# Motorcontroller.net
KiCad netlist of a schematic drawn in EAGLE
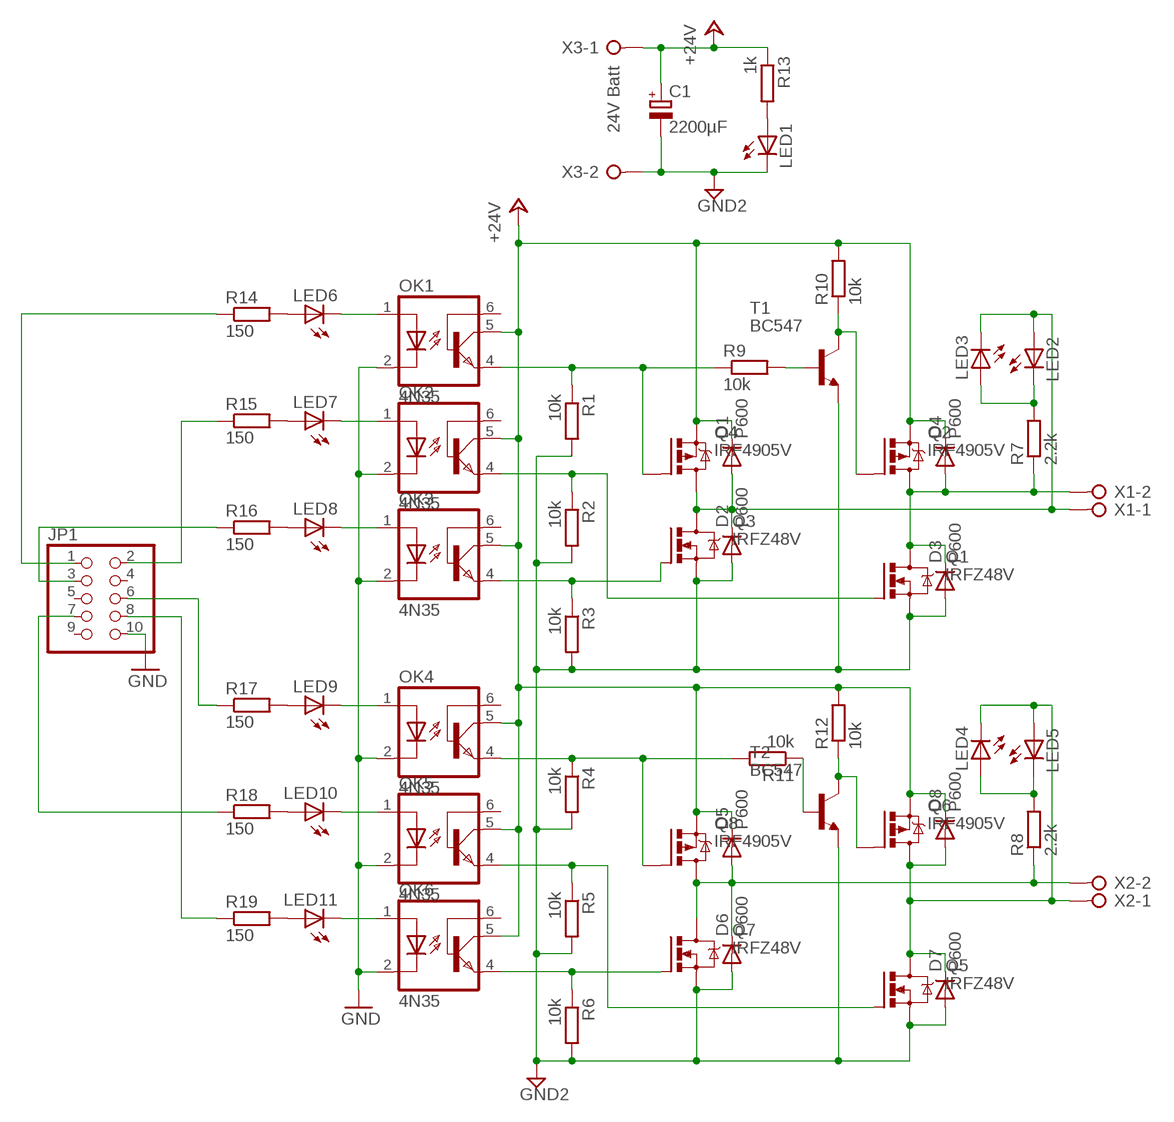
[diagram p0: schematic, sheet 1]

(export (version "E")
  (design (tool "Eeschema 10.0.6"))
  (components
    (comp (ref "C1")
      (value "2200µF")
      (footprint "eagle-import:E5-13")
      (libsource (lib "eagle-import") (part "CPOL-EUE5-13"))
    )
    (comp (ref "D1")
      (value "P600")
      (footprint "eagle-import:P6-15")
      (libsource (lib "eagle-import") (part "P600"))
    )
    (comp (ref "D2")
      (value "P600")
      (footprint "eagle-import:P6-15")
      (libsource (lib "eagle-import") (part "P600"))
    )
    (comp (ref "D3")
      (value "P600")
      (footprint "eagle-import:P6-15")
      (libsource (lib "eagle-import") (part "P600"))
    )
    (comp (ref "D4")
      (value "P600")
      (footprint "eagle-import:P6-15")
      (libsource (lib "eagle-import") (part "P600"))
    )
    (comp (ref "D5")
      (value "P600")
      (footprint "eagle-import:P6-15")
      (libsource (lib "eagle-import") (part "P600"))
    )
    (comp (ref "D6")
      (value "P600")
      (footprint "eagle-import:P6-15")
      (libsource (lib "eagle-import") (part "P600"))
    )
    (comp (ref "D7")
      (value "P600")
      (footprint "eagle-import:P6-15")
      (libsource (lib "eagle-import") (part "P600"))
    )
    (comp (ref "D8")
      (value "P600")
      (footprint "eagle-import:P6-15")
      (libsource (lib "eagle-import") (part "P600"))
    )
    (comp (ref "JP1")
      (value "PINHD-2X5")
      (footprint "eagle-import:2X05")
      (libsource (lib "eagle-import") (part "PINHD-2X5"))
    )
    (comp (ref "LED1")
      (value "LED3MM")
      (footprint "eagle-import:LED3MM")
      (libsource (lib "eagle-import") (part "LED3MM"))
    )
    (comp (ref "LED2")
      (value "LED3MM")
      (footprint "eagle-import:LED3MM")
      (libsource (lib "eagle-import") (part "LED3MM"))
    )
    (comp (ref "LED3")
      (value "LED3MM")
      (footprint "eagle-import:LED3MM")
      (libsource (lib "eagle-import") (part "LED3MM"))
    )
    (comp (ref "LED4")
      (value "LED3MM")
      (footprint "eagle-import:LED3MM")
      (libsource (lib "eagle-import") (part "LED3MM"))
    )
    (comp (ref "LED5")
      (value "LED3MM")
      (footprint "eagle-import:LED3MM")
      (libsource (lib "eagle-import") (part "LED3MM"))
    )
    (comp (ref "LED6")
      (value "LED3MM")
      (footprint "eagle-import:LED3MM")
      (libsource (lib "eagle-import") (part "LED3MM"))
    )
    (comp (ref "LED7")
      (value "LED3MM")
      (footprint "eagle-import:LED3MM")
      (libsource (lib "eagle-import") (part "LED3MM"))
    )
    (comp (ref "LED8")
      (value "LED3MM")
      (footprint "eagle-import:LED3MM")
      (libsource (lib "eagle-import") (part "LED3MM"))
    )
    (comp (ref "LED9")
      (value "LED3MM")
      (footprint "eagle-import:LED3MM")
      (libsource (lib "eagle-import") (part "LED3MM"))
    )
    (comp (ref "LED10")
      (value "LED3MM")
      (footprint "eagle-import:LED3MM")
      (libsource (lib "eagle-import") (part "LED3MM"))
    )
    (comp (ref "LED11")
      (value "LED3MM")
      (footprint "eagle-import:LED3MM")
      (libsource (lib "eagle-import") (part "LED3MM"))
    )
    (comp (ref "OK1")
      (value "4N35")
      (footprint "eagle-import:DIL06")
      (fields (field (name "MF") "FAIRCHILD SEMICONDUCTOR"))
      (libsource (lib "eagle-import") (part "4N35"))
    )
    (comp (ref "OK2")
      (value "4N35")
      (footprint "eagle-import:DIL06")
      (fields (field (name "MF") "FAIRCHILD SEMICONDUCTOR"))
      (libsource (lib "eagle-import") (part "4N35"))
    )
    (comp (ref "OK3")
      (value "4N35")
      (footprint "eagle-import:DIL06")
      (fields (field (name "MF") "FAIRCHILD SEMICONDUCTOR"))
      (libsource (lib "eagle-import") (part "4N35"))
    )
    (comp (ref "OK4")
      (value "4N35")
      (footprint "eagle-import:DIL06")
      (fields (field (name "MF") "FAIRCHILD SEMICONDUCTOR"))
      (libsource (lib "eagle-import") (part "4N35"))
    )
    (comp (ref "OK5")
      (value "4N35")
      (footprint "eagle-import:DIL06")
      (fields (field (name "MF") "FAIRCHILD SEMICONDUCTOR"))
      (libsource (lib "eagle-import") (part "4N35"))
    )
    (comp (ref "OK6")
      (value "4N35")
      (footprint "eagle-import:DIL06")
      (fields (field (name "MF") "FAIRCHILD SEMICONDUCTOR"))
      (libsource (lib "eagle-import") (part "4N35"))
    )
    (comp (ref "Q1")
      (value "IRFZ48V")
      (footprint "eagle-import:TO220BV")
      (libsource (lib "eagle-import") (part "IRFZ48V"))
    )
    (comp (ref "Q2")
      (value "IRF4905V")
      (footprint "eagle-import:TO220BV")
      (libsource (lib "eagle-import") (part "IRF4905V"))
    )
    (comp (ref "Q3")
      (value "IRFZ48V")
      (footprint "eagle-import:TO220BV")
      (libsource (lib "eagle-import") (part "IRFZ48V"))
    )
    (comp (ref "Q4")
      (value "IRF4905V")
      (footprint "eagle-import:TO220BV")
      (libsource (lib "eagle-import") (part "IRF4905V"))
    )
    (comp (ref "Q5")
      (value "IRFZ48V")
      (footprint "eagle-import:TO220BV")
      (libsource (lib "eagle-import") (part "IRFZ48V"))
    )
    (comp (ref "Q6")
      (value "IRF4905V")
      (footprint "eagle-import:TO220BV")
      (libsource (lib "eagle-import") (part "IRF4905V"))
    )
    (comp (ref "Q7")
      (value "IRFZ48V")
      (footprint "eagle-import:TO220BV")
      (libsource (lib "eagle-import") (part "IRFZ48V"))
    )
    (comp (ref "Q8")
      (value "IRF4905V")
      (footprint "eagle-import:TO220BV")
      (libsource (lib "eagle-import") (part "IRF4905V"))
    )
    (comp (ref "R1")
      (value "10k")
      (footprint "eagle-import:0207_7")
      (libsource (lib "eagle-import") (part "R-EU_0207/7"))
    )
    (comp (ref "R2")
      (value "10k")
      (footprint "eagle-import:0207_7")
      (libsource (lib "eagle-import") (part "R-EU_0207/7"))
    )
    (comp (ref "R3")
      (value "10k")
      (footprint "eagle-import:0207_10")
      (libsource (lib "eagle-import") (part "R-EU_0207/10"))
    )
    (comp (ref "R4")
      (value "10k")
      (footprint "eagle-import:0207_10")
      (libsource (lib "eagle-import") (part "R-EU_0207/10"))
    )
    (comp (ref "R5")
      (value "10k")
      (footprint "eagle-import:0207_10")
      (libsource (lib "eagle-import") (part "R-EU_0207/10"))
    )
    (comp (ref "R6")
      (value "10k")
      (footprint "eagle-import:0207_10")
      (libsource (lib "eagle-import") (part "R-EU_0207/10"))
    )
    (comp (ref "R7")
      (value "2.2k")
      (footprint "eagle-import:0207_2V")
      (libsource (lib "eagle-import") (part "R-EU_0207/2V"))
    )
    (comp (ref "R8")
      (value "2.2k")
      (footprint "eagle-import:0207_2V")
      (libsource (lib "eagle-import") (part "R-EU_0207/2V"))
    )
    (comp (ref "R9")
      (value "10k")
      (footprint "eagle-import:0207_7")
      (libsource (lib "eagle-import") (part "R-EU_0207/7"))
    )
    (comp (ref "R10")
      (value "10k")
      (footprint "eagle-import:0207_7")
      (libsource (lib "eagle-import") (part "R-EU_0207/7"))
    )
    (comp (ref "R11")
      (value "10k")
      (footprint "eagle-import:0207_10")
      (libsource (lib "eagle-import") (part "R-EU_0207/10"))
    )
    (comp (ref "R12")
      (value "10k")
      (footprint "eagle-import:0207_10")
      (libsource (lib "eagle-import") (part "R-EU_0207/10"))
    )
    (comp (ref "R13")
      (value "1k")
      (footprint "eagle-import:0207_2V")
      (libsource (lib "eagle-import") (part "R-EU_0207/2V"))
    )
    (comp (ref "R14")
      (value "150")
      (footprint "eagle-import:0207_7")
      (libsource (lib "eagle-import") (part "R-EU_0207/7"))
    )
    (comp (ref "R15")
      (value "150")
      (footprint "eagle-import:0207_5V")
      (libsource (lib "eagle-import") (part "R-EU_0207/5V"))
    )
    (comp (ref "R16")
      (value "150")
      (footprint "eagle-import:0207_5V")
      (libsource (lib "eagle-import") (part "R-EU_0207/5V"))
    )
    (comp (ref "R17")
      (value "150")
      (footprint "eagle-import:0207_5V")
      (libsource (lib "eagle-import") (part "R-EU_0207/5V"))
    )
    (comp (ref "R18")
      (value "150")
      (footprint "eagle-import:0207_5V")
      (libsource (lib "eagle-import") (part "R-EU_0207/5V"))
    )
    (comp (ref "R19")
      (value "150")
      (footprint "eagle-import:0207_7")
      (libsource (lib "eagle-import") (part "R-EU_0207/7"))
    )
    (comp (ref "T1")
      (value "BC547")
      (footprint "eagle-import:TO92")
      (libsource (lib "eagle-import") (part "BC547"))
    )
    (comp (ref "T2")
      (value "BC547")
      (footprint "eagle-import:TO92")
      (libsource (lib "eagle-import") (part "BC547"))
    )
    (comp (ref "X1")
      (value "W237-02P")
      (footprint "eagle-import:W237-132")
      (fields (field (name "OC_FARNELL") "unknown") (field (name "OC_NEWARK") "unknown"))
      (libsource (lib "eagle-import") (part "W237-02P"))
    )
    (comp (ref "X2")
      (value "W237-02P")
      (footprint "eagle-import:W237-132")
      (fields (field (name "OC_FARNELL") "unknown") (field (name "OC_NEWARK") "unknown"))
      (libsource (lib "eagle-import") (part "W237-02P"))
    )
    (comp (ref "X3")
      (value "24V Batt")
      (footprint "eagle-import:W237-132")
      (fields (field (name "OC_FARNELL") "unknown") (field (name "OC_NEWARK") "unknown"))
      (libsource (lib "eagle-import") (part "W237-02P"))
    )
  )
  (nets
    (net (code "1") (name "+24V") (class "Default")
      (node (ref "C1") (pin "+") (pinfunction "+_+") (pintype "passive"))
      (node (ref "D1") (pin "C") (pinfunction "C_C") (pintype "passive"))
      (node (ref "D4") (pin "C") (pinfunction "C_C") (pintype "passive"))
      (node (ref "D5") (pin "C") (pinfunction "C_C") (pintype "passive"))
      (node (ref "D8") (pin "C") (pinfunction "C_C") (pintype "passive"))
      (node (ref "OK1") (pin "5") (pinfunction "COL_5") (pintype "passive"))
      (node (ref "OK2") (pin "5") (pinfunction "COL_5") (pintype "passive"))
      (node (ref "OK3") (pin "5") (pinfunction "COL_5") (pintype "passive"))
      (node (ref "OK4") (pin "5") (pinfunction "COL_5") (pintype "passive"))
      (node (ref "OK5") (pin "5") (pinfunction "COL_5") (pintype "passive"))
      (node (ref "OK6") (pin "5") (pinfunction "COL_5") (pintype "passive"))
      (node (ref "Q2") (pin "S") (pinfunction "S_S") (pintype "passive"))
      (node (ref "Q4") (pin "S") (pinfunction "S_S") (pintype "passive"))
      (node (ref "Q6") (pin "S") (pinfunction "S_S") (pintype "passive"))
      (node (ref "Q8") (pin "S") (pinfunction "S_S") (pintype "passive"))
      (node (ref "R10") (pin "2") (pinfunction "2_2") (pintype "passive"))
      (node (ref "R12") (pin "2") (pinfunction "2_2") (pintype "passive"))
      (node (ref "R13") (pin "1") (pinfunction "1_1") (pintype "passive"))
      (node (ref "X3") (pin "1") (pinfunction "KL_1") (pintype "passive"))
    )
    (net (code "2") (name "GND") (class "Default")
      (node (ref "JP1") (pin "10") (pinfunction "10_10") (pintype "passive"))
      (node (ref "OK1") (pin "2") (pinfunction "C_2") (pintype "passive"))
      (node (ref "OK2") (pin "2") (pinfunction "C_2") (pintype "passive"))
      (node (ref "OK3") (pin "2") (pinfunction "C_2") (pintype "passive"))
      (node (ref "OK4") (pin "2") (pinfunction "C_2") (pintype "passive"))
      (node (ref "OK5") (pin "2") (pinfunction "C_2") (pintype "passive"))
      (node (ref "OK6") (pin "2") (pinfunction "C_2") (pintype "passive"))
    )
    (net (code "3") (name "GND2") (class "Default")
      (node (ref "C1") (pin "-") (pinfunction "-_-") (pintype "passive"))
      (node (ref "D2") (pin "A") (pinfunction "A_A") (pintype "passive"))
      (node (ref "D3") (pin "A") (pinfunction "A_A") (pintype "passive"))
      (node (ref "D6") (pin "A") (pinfunction "A_A") (pintype "passive"))
      (node (ref "D7") (pin "A") (pinfunction "A_A") (pintype "passive"))
      (node (ref "LED1") (pin "K") (pinfunction "C_K") (pintype "passive"))
      (node (ref "Q1") (pin "S") (pinfunction "S_S") (pintype "passive"))
      (node (ref "Q3") (pin "S") (pinfunction "S_S") (pintype "passive"))
      (node (ref "Q5") (pin "S") (pinfunction "S_S") (pintype "passive"))
      (node (ref "Q7") (pin "S") (pinfunction "S_S") (pintype "passive"))
      (node (ref "R1") (pin "2") (pinfunction "2_2") (pintype "passive"))
      (node (ref "R2") (pin "2") (pinfunction "2_2") (pintype "passive"))
      (node (ref "R3") (pin "2") (pinfunction "2_2") (pintype "passive"))
      (node (ref "R4") (pin "2") (pinfunction "2_2") (pintype "passive"))
      (node (ref "R5") (pin "2") (pinfunction "2_2") (pintype "passive"))
      (node (ref "R6") (pin "2") (pinfunction "2_2") (pintype "passive"))
      (node (ref "T1") (pin "1") (pinfunction "E_1") (pintype "passive"))
      (node (ref "T2") (pin "1") (pinfunction "E_1") (pintype "passive"))
      (node (ref "X3") (pin "2") (pinfunction "KL_2") (pintype "passive"))
    )
    (net (code "4") (name "Net-(JP1-Pad1)") (class "Default")
      (node (ref "JP1") (pin "1") (pinfunction "1_1") (pintype "passive"))
      (node (ref "R14") (pin "1") (pinfunction "1_1") (pintype "passive"))
    )
    (net (code "5") (name "Net-(JP1-Pad2)") (class "Default")
      (node (ref "JP1") (pin "2") (pinfunction "2_2") (pintype "passive"))
      (node (ref "R15") (pin "1") (pinfunction "1_1") (pintype "passive"))
    )
    (net (code "6") (name "Net-(JP1-Pad3)") (class "Default")
      (node (ref "JP1") (pin "3") (pinfunction "3_3") (pintype "passive"))
      (node (ref "R16") (pin "1") (pinfunction "1_1") (pintype "passive"))
    )
    (net (code "7") (name "Net-(JP1-Pad6)") (class "Default")
      (node (ref "JP1") (pin "6") (pinfunction "6_6") (pintype "passive"))
      (node (ref "R17") (pin "1") (pinfunction "1_1") (pintype "passive"))
    )
    (net (code "8") (name "Net-(JP1-Pad7)") (class "Default")
      (node (ref "JP1") (pin "7") (pinfunction "7_7") (pintype "passive"))
      (node (ref "R18") (pin "1") (pinfunction "1_1") (pintype "passive"))
    )
    (net (code "9") (name "Net-(JP1-Pad8)") (class "Default")
      (node (ref "JP1") (pin "8") (pinfunction "8_8") (pintype "passive"))
      (node (ref "R19") (pin "1") (pinfunction "1_1") (pintype "passive"))
    )
    (net (code "10") (name "Net-(LED1-PadA)") (class "Default")
      (node (ref "LED1") (pin "A") (pinfunction "A_A") (pintype "passive"))
      (node (ref "R13") (pin "2") (pinfunction "2_2") (pintype "passive"))
    )
    (net (code "11") (name "Net-(LED2-C)") (class "Default")
      (node (ref "LED2") (pin "K") (pinfunction "C_K") (pintype "passive"))
      (node (ref "LED3") (pin "A") (pinfunction "A_A") (pintype "passive"))
      (node (ref "R7") (pin "2") (pinfunction "2_2") (pintype "passive"))
    )
    (net (code "12") (name "Net-(LED3-C)") (class "Default")
      (node (ref "D1") (pin "A") (pinfunction "A_A") (pintype "passive"))
      (node (ref "D2") (pin "C") (pinfunction "C_C") (pintype "passive"))
      (node (ref "LED2") (pin "A") (pinfunction "A_A") (pintype "passive"))
      (node (ref "LED3") (pin "K") (pinfunction "C_K") (pintype "passive"))
      (node (ref "Q3") (pin "D") (pinfunction "D_D") (pintype "passive"))
      (node (ref "Q4") (pin "D") (pinfunction "D_D") (pintype "passive"))
      (node (ref "X1") (pin "1") (pinfunction "KL_1") (pintype "passive"))
    )
    (net (code "13") (name "Net-(LED4-C)") (class "Default")
      (node (ref "D7") (pin "C") (pinfunction "C_C") (pintype "passive"))
      (node (ref "D8") (pin "A") (pinfunction "A_A") (pintype "passive"))
      (node (ref "LED4") (pin "K") (pinfunction "C_K") (pintype "passive"))
      (node (ref "LED5") (pin "A") (pinfunction "A_A") (pintype "passive"))
      (node (ref "Q5") (pin "D") (pinfunction "D_D") (pintype "passive"))
      (node (ref "Q6") (pin "D") (pinfunction "D_D") (pintype "passive"))
      (node (ref "X2") (pin "1") (pinfunction "KL_1") (pintype "passive"))
    )
    (net (code "14") (name "Net-(LED5-C)") (class "Default")
      (node (ref "LED4") (pin "A") (pinfunction "A_A") (pintype "passive"))
      (node (ref "LED5") (pin "K") (pinfunction "C_K") (pintype "passive"))
      (node (ref "R8") (pin "2") (pinfunction "2_2") (pintype "passive"))
    )
    (net (code "15") (name "Net-(LED6-C)") (class "Default")
      (node (ref "LED6") (pin "K") (pinfunction "C_K") (pintype "passive"))
      (node (ref "OK1") (pin "1") (pinfunction "A_1") (pintype "passive"))
    )
    (net (code "16") (name "Net-(LED6-PadA)") (class "Default")
      (node (ref "LED6") (pin "A") (pinfunction "A_A") (pintype "passive"))
      (node (ref "R14") (pin "2") (pinfunction "2_2") (pintype "passive"))
    )
    (net (code "17") (name "Net-(LED7-C)") (class "Default")
      (node (ref "LED7") (pin "K") (pinfunction "C_K") (pintype "passive"))
      (node (ref "OK2") (pin "1") (pinfunction "A_1") (pintype "passive"))
    )
    (net (code "18") (name "Net-(LED7-PadA)") (class "Default")
      (node (ref "LED7") (pin "A") (pinfunction "A_A") (pintype "passive"))
      (node (ref "R15") (pin "2") (pinfunction "2_2") (pintype "passive"))
    )
    (net (code "19") (name "Net-(LED8-C)") (class "Default")
      (node (ref "LED8") (pin "K") (pinfunction "C_K") (pintype "passive"))
      (node (ref "OK3") (pin "1") (pinfunction "A_1") (pintype "passive"))
    )
    (net (code "20") (name "Net-(LED8-PadA)") (class "Default")
      (node (ref "LED8") (pin "A") (pinfunction "A_A") (pintype "passive"))
      (node (ref "R16") (pin "2") (pinfunction "2_2") (pintype "passive"))
    )
    (net (code "21") (name "Net-(LED9-C)") (class "Default")
      (node (ref "LED9") (pin "K") (pinfunction "C_K") (pintype "passive"))
      (node (ref "OK4") (pin "1") (pinfunction "A_1") (pintype "passive"))
    )
    (net (code "22") (name "Net-(LED9-PadA)") (class "Default")
      (node (ref "LED9") (pin "A") (pinfunction "A_A") (pintype "passive"))
      (node (ref "R17") (pin "2") (pinfunction "2_2") (pintype "passive"))
    )
    (net (code "23") (name "Net-(LED10-C)") (class "Default")
      (node (ref "LED10") (pin "K") (pinfunction "C_K") (pintype "passive"))
      (node (ref "OK5") (pin "1") (pinfunction "A_1") (pintype "passive"))
    )
    (net (code "24") (name "Net-(LED10-PadA)") (class "Default")
      (node (ref "LED10") (pin "A") (pinfunction "A_A") (pintype "passive"))
      (node (ref "R18") (pin "2") (pinfunction "2_2") (pintype "passive"))
    )
    (net (code "25") (name "Net-(LED11-C)") (class "Default")
      (node (ref "LED11") (pin "K") (pinfunction "C_K") (pintype "passive"))
      (node (ref "OK6") (pin "1") (pinfunction "A_1") (pintype "passive"))
    )
    (net (code "26") (name "Net-(LED11-PadA)") (class "Default")
      (node (ref "LED11") (pin "A") (pinfunction "A_A") (pintype "passive"))
      (node (ref "R19") (pin "2") (pinfunction "2_2") (pintype "passive"))
    )
    (net (code "27") (name "Net-(OK1-EMI)") (class "Default")
      (node (ref "OK1") (pin "4") (pinfunction "EMI_4") (pintype "passive"))
      (node (ref "Q4") (pin "G") (pinfunction "G_G") (pintype "passive"))
      (node (ref "R1") (pin "1") (pinfunction "1_1") (pintype "passive"))
      (node (ref "R9") (pin "1") (pinfunction "1_1") (pintype "passive"))
    )
    (net (code "28") (name "Net-(OK2-EMI)") (class "Default")
      (node (ref "OK2") (pin "4") (pinfunction "EMI_4") (pintype "passive"))
      (node (ref "Q1") (pin "G") (pinfunction "G_G") (pintype "passive"))
      (node (ref "R2") (pin "1") (pinfunction "1_1") (pintype "passive"))
    )
    (net (code "29") (name "Net-(OK3-EMI)") (class "Default")
      (node (ref "OK3") (pin "4") (pinfunction "EMI_4") (pintype "passive"))
      (node (ref "Q3") (pin "G") (pinfunction "G_G") (pintype "passive"))
      (node (ref "R3") (pin "1") (pinfunction "1_1") (pintype "passive"))
    )
    (net (code "30") (name "Net-(OK4-EMI)") (class "Default")
      (node (ref "OK4") (pin "4") (pinfunction "EMI_4") (pintype "passive"))
      (node (ref "Q8") (pin "G") (pinfunction "G_G") (pintype "passive"))
      (node (ref "R11") (pin "2") (pinfunction "2_2") (pintype "passive"))
      (node (ref "R4") (pin "1") (pinfunction "1_1") (pintype "passive"))
    )
    (net (code "31") (name "Net-(OK5-EMI)") (class "Default")
      (node (ref "OK5") (pin "4") (pinfunction "EMI_4") (pintype "passive"))
      (node (ref "Q5") (pin "G") (pinfunction "G_G") (pintype "passive"))
      (node (ref "R5") (pin "1") (pinfunction "1_1") (pintype "passive"))
    )
    (net (code "32") (name "Net-(OK6-EMI)") (class "Default")
      (node (ref "OK6") (pin "4") (pinfunction "EMI_4") (pintype "passive"))
      (node (ref "Q7") (pin "G") (pinfunction "G_G") (pintype "passive"))
      (node (ref "R6") (pin "1") (pinfunction "1_1") (pintype "passive"))
    )
    (net (code "33") (name "Net-(T1-B)") (class "Default")
      (node (ref "R9") (pin "2") (pinfunction "2_2") (pintype "passive"))
      (node (ref "T1") (pin "2") (pinfunction "B_2") (pintype "passive"))
    )
    (net (code "34") (name "Net-(T1-C)") (class "Default")
      (node (ref "Q2") (pin "G") (pinfunction "G_G") (pintype "passive"))
      (node (ref "R10") (pin "1") (pinfunction "1_1") (pintype "passive"))
      (node (ref "T1") (pin "3") (pinfunction "C_3") (pintype "passive"))
    )
    (net (code "35") (name "Net-(T2-B)") (class "Default")
      (node (ref "R11") (pin "1") (pinfunction "1_1") (pintype "passive"))
      (node (ref "T2") (pin "2") (pinfunction "B_2") (pintype "passive"))
    )
    (net (code "36") (name "Net-(T2-C)") (class "Default")
      (node (ref "Q6") (pin "G") (pinfunction "G_G") (pintype "passive"))
      (node (ref "R12") (pin "1") (pinfunction "1_1") (pintype "passive"))
      (node (ref "T2") (pin "3") (pinfunction "C_3") (pintype "passive"))
    )
    (net (code "37") (name "Net-(X1B-KL)") (class "Default")
      (node (ref "D3") (pin "C") (pinfunction "C_C") (pintype "passive"))
      (node (ref "D4") (pin "A") (pinfunction "A_A") (pintype "passive"))
      (node (ref "Q1") (pin "D") (pinfunction "D_D") (pintype "passive"))
      (node (ref "Q2") (pin "D") (pinfunction "D_D") (pintype "passive"))
      (node (ref "R7") (pin "1") (pinfunction "1_1") (pintype "passive"))
      (node (ref "X1") (pin "2") (pinfunction "KL_2") (pintype "passive"))
    )
    (net (code "38") (name "Net-(X2B-KL)") (class "Default")
      (node (ref "D5") (pin "A") (pinfunction "A_A") (pintype "passive"))
      (node (ref "D6") (pin "C") (pinfunction "C_C") (pintype "passive"))
      (node (ref "Q7") (pin "D") (pinfunction "D_D") (pintype "passive"))
      (node (ref "Q8") (pin "D") (pinfunction "D_D") (pintype "passive"))
      (node (ref "R8") (pin "1") (pinfunction "1_1") (pintype "passive"))
      (node (ref "X2") (pin "2") (pinfunction "KL_2") (pintype "passive"))
    )
    (net (code "39") (name "unconnected-(JP1-Pad4)") (class "Default")
      (node (ref "JP1") (pin "4") (pinfunction "4_4") (pintype "passive"))
    )
    (net (code "40") (name "unconnected-(JP1-Pad5)") (class "Default")
      (node (ref "JP1") (pin "5") (pinfunction "5_5") (pintype "passive"))
    )
    (net (code "41") (name "unconnected-(JP1-Pad9)") (class "Default")
      (node (ref "JP1") (pin "9") (pinfunction "9_9") (pintype "passive"))
    )
    (net (code "42") (name "unconnected-(OK1-BAS-Pad6)") (class "Default")
      (node (ref "OK1") (pin "6") (pinfunction "BAS_6") (pintype "passive"))
    )
    (net (code "43") (name "unconnected-(OK2-BAS-Pad6)") (class "Default")
      (node (ref "OK2") (pin "6") (pinfunction "BAS_6") (pintype "passive"))
    )
    (net (code "44") (name "unconnected-(OK3-BAS-Pad6)") (class "Default")
      (node (ref "OK3") (pin "6") (pinfunction "BAS_6") (pintype "passive"))
    )
    (net (code "45") (name "unconnected-(OK4-BAS-Pad6)") (class "Default")
      (node (ref "OK4") (pin "6") (pinfunction "BAS_6") (pintype "passive"))
    )
    (net (code "46") (name "unconnected-(OK5-BAS-Pad6)") (class "Default")
      (node (ref "OK5") (pin "6") (pinfunction "BAS_6") (pintype "passive"))
    )
    (net (code "47") (name "unconnected-(OK6-BAS-Pad6)") (class "Default")
      (node (ref "OK6") (pin "6") (pinfunction "BAS_6") (pintype "passive"))
    )
  )
)
